# project_pcb.net
KiCad netlist of a schematic drawn in EAGLE
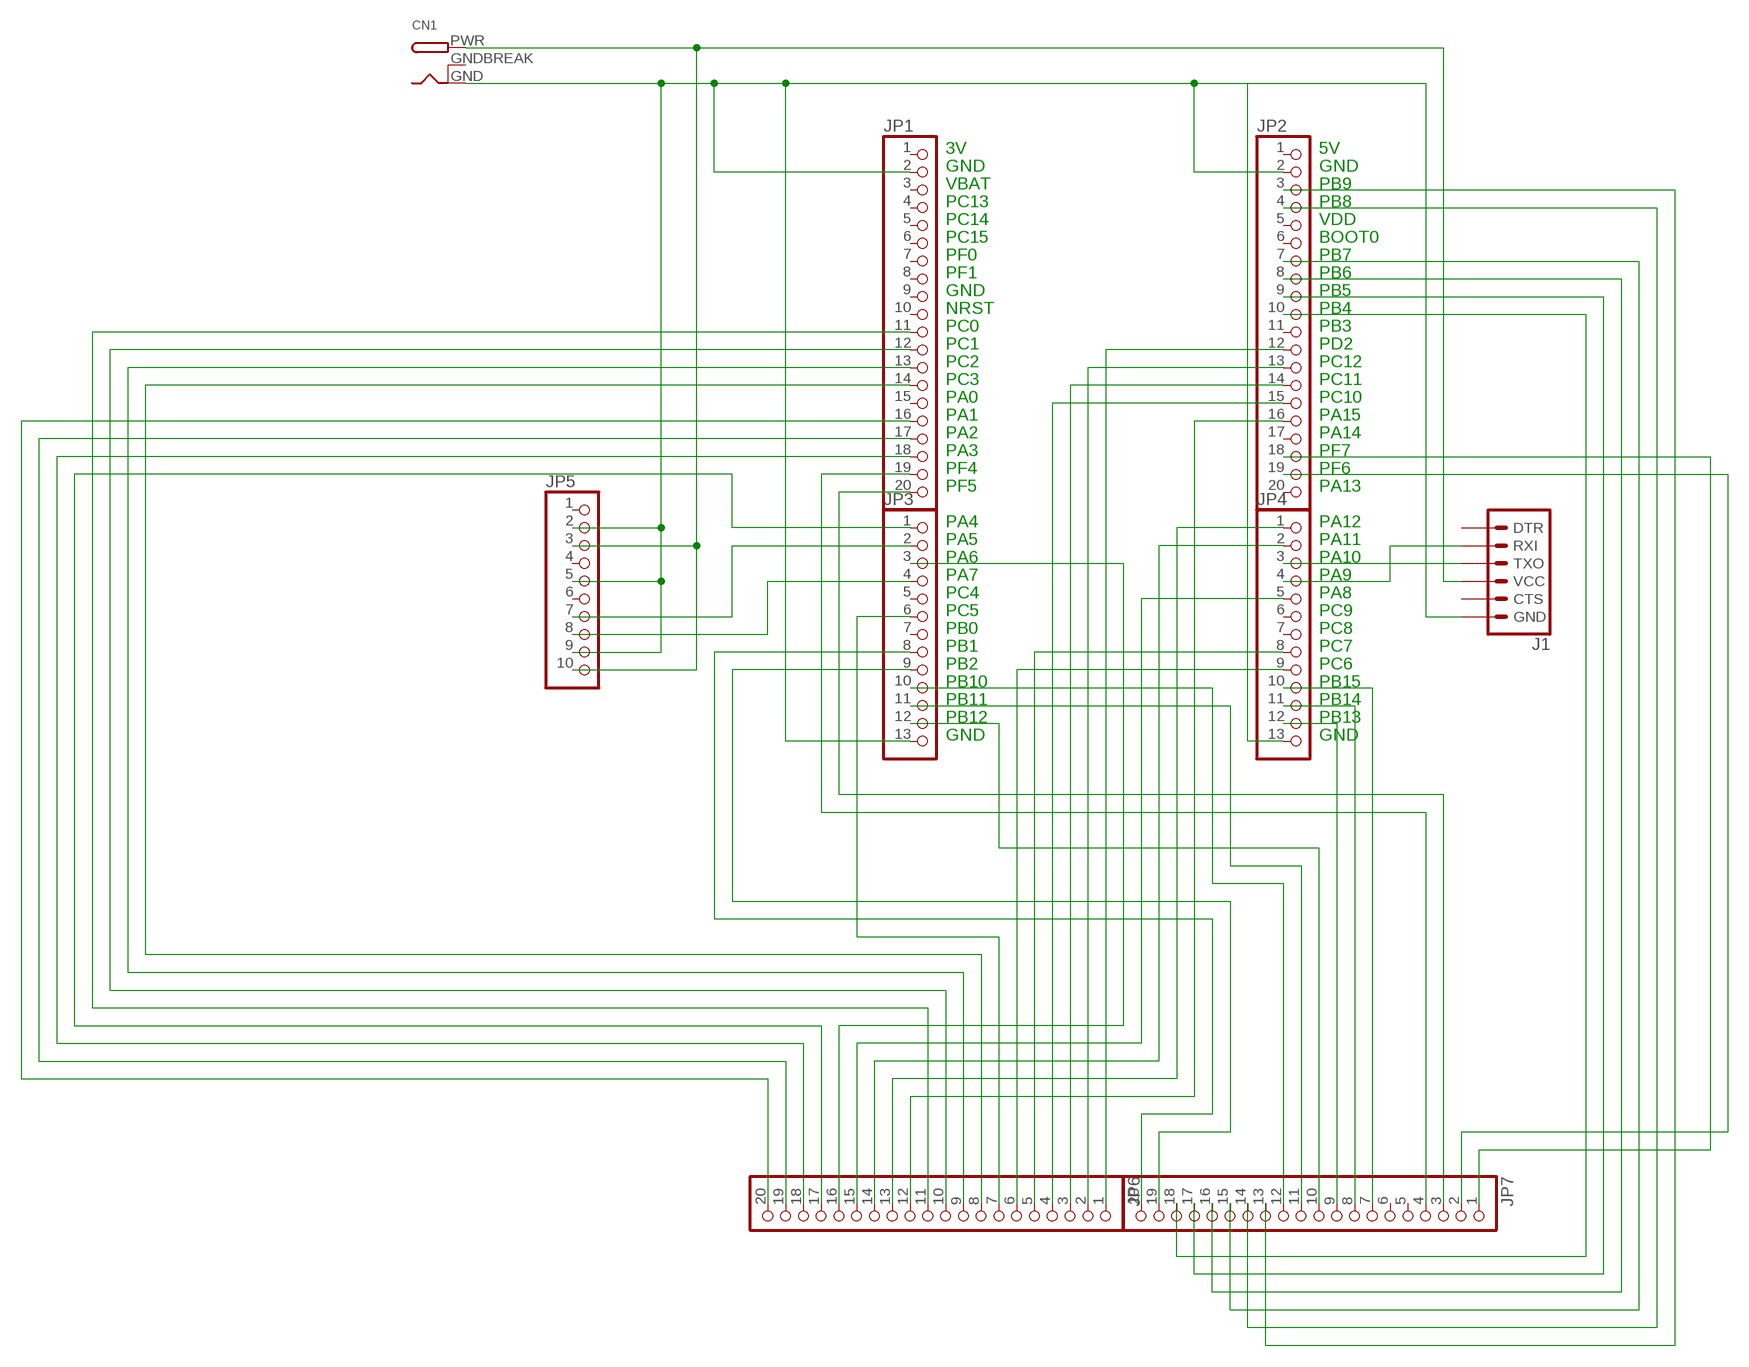
[diagram p0: schematic, sheet 1]

(export (version "E")
  (design (tool "Eeschema 10.0.6"))
  (components
    (comp (ref "CN1")
      (value "DCBARRELPTH")
      (footprint "eagle-import:DCJACK_2MM_PTH")
      (libsource (lib "eagle-import") (part "DCBARRELPTH"))
    )
    (comp (ref "J1")
      (value "6_PIN_SERIAL_TARGET")
      (footprint "eagle-import:1X06")
      (libsource (lib "eagle-import") (part "6_PIN_SERIAL_TARGET"))
    )
    (comp (ref "JP1")
      (value "PINHD-1X20")
      (footprint "eagle-import:1X20")
      (libsource (lib "eagle-import") (part "PINHD-1X20"))
    )
    (comp (ref "JP2")
      (value "PINHD-1X20")
      (footprint "eagle-import:1X20")
      (libsource (lib "eagle-import") (part "PINHD-1X20"))
    )
    (comp (ref "JP3")
      (value "PINHD-1X13")
      (footprint "eagle-import:1X13")
      (libsource (lib "eagle-import") (part "PINHD-1X13"))
    )
    (comp (ref "JP4")
      (value "PINHD-1X13")
      (footprint "eagle-import:1X13")
      (libsource (lib "eagle-import") (part "PINHD-1X13"))
    )
    (comp (ref "JP5")
      (value "PINHD-1X10")
      (footprint "eagle-import:1X10")
      (libsource (lib "eagle-import") (part "PINHD-1X10"))
    )
    (comp (ref "JP6")
      (value "PINHD-1X20")
      (footprint "eagle-import:1X20")
      (libsource (lib "eagle-import") (part "PINHD-1X20"))
    )
    (comp (ref "JP7")
      (value "PINHD-1X20")
      (footprint "eagle-import:1X20")
      (libsource (lib "eagle-import") (part "PINHD-1X20"))
    )
  )
  (nets
    (net (code "1") (name "/GNDBREAK") (class "Default")
      (node (ref "CN1") (pin "GNDBREAK") (pinfunction "GNDBREAK_GNDBREAK") (pintype "power_in"))
    )
    (net (code "2") (name "Net-(J1-GND)") (class "Default")
      (node (ref "CN1") (pin "GND") (pinfunction "GND_GND") (pintype "power_in"))
      (node (ref "J1") (pin "6") (pinfunction "GND_6") (pintype "passive"))
      (node (ref "JP1") (pin "2") (pinfunction "2_2") (pintype "passive"))
      (node (ref "JP2") (pin "2") (pinfunction "2_2") (pintype "passive"))
      (node (ref "JP3") (pin "13") (pinfunction "13_13") (pintype "passive"))
      (node (ref "JP4") (pin "13") (pinfunction "13_13") (pintype "passive"))
      (node (ref "JP5") (pin "2") (pinfunction "2_2") (pintype "passive"))
      (node (ref "JP5") (pin "5") (pinfunction "5_5") (pintype "passive"))
      (node (ref "JP5") (pin "9") (pinfunction "9_9") (pintype "passive"))
    )
    (net (code "3") (name "Net-(J1-RXI)") (class "Default")
      (node (ref "J1") (pin "2") (pinfunction "RXI_2") (pintype "passive"))
      (node (ref "JP4") (pin "4") (pinfunction "4_4") (pintype "passive"))
    )
    (net (code "4") (name "Net-(J1-TXO)") (class "Default")
      (node (ref "J1") (pin "3") (pinfunction "TXO_3") (pintype "passive"))
      (node (ref "JP4") (pin "3") (pinfunction "3_3") (pintype "passive"))
    )
    (net (code "5") (name "Net-(J1-VCC)") (class "Default")
      (node (ref "CN1") (pin "PWR") (pinfunction "PWR_PWR") (pintype "power_in"))
      (node (ref "J1") (pin "4") (pinfunction "VCC_4") (pintype "passive"))
      (node (ref "JP5") (pin "10") (pinfunction "10_10") (pintype "passive"))
      (node (ref "JP5") (pin "3") (pinfunction "3_3") (pintype "passive"))
    )
    (net (code "6") (name "Net-(JP1-Pad11)") (class "Default")
      (node (ref "JP1") (pin "11") (pinfunction "11_11") (pintype "passive"))
      (node (ref "JP6") (pin "11") (pinfunction "11_11") (pintype "passive"))
    )
    (net (code "7") (name "Net-(JP1-Pad12)") (class "Default")
      (node (ref "JP1") (pin "12") (pinfunction "12_12") (pintype "passive"))
      (node (ref "JP6") (pin "10") (pinfunction "10_10") (pintype "passive"))
    )
    (net (code "8") (name "Net-(JP1-Pad13)") (class "Default")
      (node (ref "JP1") (pin "13") (pinfunction "13_13") (pintype "passive"))
      (node (ref "JP6") (pin "9") (pinfunction "9_9") (pintype "passive"))
    )
    (net (code "9") (name "Net-(JP1-Pad14)") (class "Default")
      (node (ref "JP1") (pin "14") (pinfunction "14_14") (pintype "passive"))
      (node (ref "JP6") (pin "8") (pinfunction "8_8") (pintype "passive"))
    )
    (net (code "10") (name "Net-(JP1-Pad16)") (class "Default")
      (node (ref "JP1") (pin "16") (pinfunction "16_16") (pintype "passive"))
      (node (ref "JP6") (pin "20") (pinfunction "20_20") (pintype "passive"))
    )
    (net (code "11") (name "Net-(JP1-Pad17)") (class "Default")
      (node (ref "JP1") (pin "17") (pinfunction "17_17") (pintype "passive"))
      (node (ref "JP6") (pin "19") (pinfunction "19_19") (pintype "passive"))
    )
    (net (code "12") (name "Net-(JP1-Pad18)") (class "Default")
      (node (ref "JP1") (pin "18") (pinfunction "18_18") (pintype "passive"))
      (node (ref "JP6") (pin "18") (pinfunction "18_18") (pintype "passive"))
    )
    (net (code "13") (name "Net-(JP1-Pad19)") (class "Default")
      (node (ref "JP1") (pin "19") (pinfunction "19_19") (pintype "passive"))
      (node (ref "JP7") (pin "4") (pinfunction "4_4") (pintype "passive"))
    )
    (net (code "14") (name "Net-(JP1-Pad20)") (class "Default")
      (node (ref "JP1") (pin "20") (pinfunction "20_20") (pintype "passive"))
      (node (ref "JP7") (pin "3") (pinfunction "3_3") (pintype "passive"))
    )
    (net (code "15") (name "Net-(JP2-Pad3)") (class "Default")
      (node (ref "JP2") (pin "3") (pinfunction "3_3") (pintype "passive"))
      (node (ref "JP7") (pin "13") (pinfunction "13_13") (pintype "passive"))
    )
    (net (code "16") (name "Net-(JP2-Pad4)") (class "Default")
      (node (ref "JP2") (pin "4") (pinfunction "4_4") (pintype "passive"))
      (node (ref "JP7") (pin "14") (pinfunction "14_14") (pintype "passive"))
    )
    (net (code "17") (name "Net-(JP2-Pad7)") (class "Default")
      (node (ref "JP2") (pin "7") (pinfunction "7_7") (pintype "passive"))
      (node (ref "JP7") (pin "15") (pinfunction "15_15") (pintype "passive"))
    )
    (net (code "18") (name "Net-(JP2-Pad8)") (class "Default")
      (node (ref "JP2") (pin "8") (pinfunction "8_8") (pintype "passive"))
      (node (ref "JP7") (pin "16") (pinfunction "16_16") (pintype "passive"))
    )
    (net (code "19") (name "Net-(JP2-Pad9)") (class "Default")
      (node (ref "JP2") (pin "9") (pinfunction "9_9") (pintype "passive"))
      (node (ref "JP7") (pin "17") (pinfunction "17_17") (pintype "passive"))
    )
    (net (code "20") (name "Net-(JP2-Pad10)") (class "Default")
      (node (ref "JP2") (pin "10") (pinfunction "10_10") (pintype "passive"))
      (node (ref "JP7") (pin "18") (pinfunction "18_18") (pintype "passive"))
    )
    (net (code "21") (name "Net-(JP2-Pad12)") (class "Default")
      (node (ref "JP2") (pin "12") (pinfunction "12_12") (pintype "passive"))
      (node (ref "JP6") (pin "1") (pinfunction "1_1") (pintype "passive"))
    )
    (net (code "22") (name "Net-(JP2-Pad13)") (class "Default")
      (node (ref "JP2") (pin "13") (pinfunction "13_13") (pintype "passive"))
      (node (ref "JP6") (pin "2") (pinfunction "2_2") (pintype "passive"))
    )
    (net (code "23") (name "Net-(JP2-Pad14)") (class "Default")
      (node (ref "JP2") (pin "14") (pinfunction "14_14") (pintype "passive"))
      (node (ref "JP6") (pin "3") (pinfunction "3_3") (pintype "passive"))
    )
    (net (code "24") (name "Net-(JP2-Pad15)") (class "Default")
      (node (ref "JP2") (pin "15") (pinfunction "15_15") (pintype "passive"))
      (node (ref "JP6") (pin "4") (pinfunction "4_4") (pintype "passive"))
    )
    (net (code "25") (name "Net-(JP2-Pad16)") (class "Default")
      (node (ref "JP2") (pin "16") (pinfunction "16_16") (pintype "passive"))
      (node (ref "JP6") (pin "12") (pinfunction "12_12") (pintype "passive"))
    )
    (net (code "26") (name "Net-(JP2-Pad18)") (class "Default")
      (node (ref "JP2") (pin "18") (pinfunction "18_18") (pintype "passive"))
      (node (ref "JP7") (pin "1") (pinfunction "1_1") (pintype "passive"))
    )
    (net (code "27") (name "Net-(JP2-Pad19)") (class "Default")
      (node (ref "JP2") (pin "19") (pinfunction "19_19") (pintype "passive"))
      (node (ref "JP7") (pin "2") (pinfunction "2_2") (pintype "passive"))
    )
    (net (code "28") (name "Net-(JP3-Pad1)") (class "Default")
      (node (ref "JP3") (pin "1") (pinfunction "1_1") (pintype "passive"))
      (node (ref "JP6") (pin "17") (pinfunction "17_17") (pintype "passive"))
    )
    (net (code "29") (name "Net-(JP3-Pad2)") (class "Default")
      (node (ref "JP3") (pin "2") (pinfunction "2_2") (pintype "passive"))
      (node (ref "JP5") (pin "7") (pinfunction "7_7") (pintype "passive"))
    )
    (net (code "30") (name "Net-(JP3-Pad3)") (class "Default")
      (node (ref "JP3") (pin "3") (pinfunction "3_3") (pintype "passive"))
      (node (ref "JP6") (pin "16") (pinfunction "16_16") (pintype "passive"))
    )
    (net (code "31") (name "Net-(JP3-Pad4)") (class "Default")
      (node (ref "JP3") (pin "4") (pinfunction "4_4") (pintype "passive"))
      (node (ref "JP5") (pin "8") (pinfunction "8_8") (pintype "passive"))
    )
    (net (code "32") (name "Net-(JP3-Pad6)") (class "Default")
      (node (ref "JP3") (pin "6") (pinfunction "6_6") (pintype "passive"))
      (node (ref "JP6") (pin "7") (pinfunction "7_7") (pintype "passive"))
    )
    (net (code "33") (name "Net-(JP3-Pad8)") (class "Default")
      (node (ref "JP3") (pin "8") (pinfunction "8_8") (pintype "passive"))
      (node (ref "JP7") (pin "20") (pinfunction "20_20") (pintype "passive"))
    )
    (net (code "34") (name "Net-(JP3-Pad9)") (class "Default")
      (node (ref "JP3") (pin "9") (pinfunction "9_9") (pintype "passive"))
      (node (ref "JP7") (pin "19") (pinfunction "19_19") (pintype "passive"))
    )
    (net (code "35") (name "Net-(JP3-Pad10)") (class "Default")
      (node (ref "JP3") (pin "10") (pinfunction "10_10") (pintype "passive"))
      (node (ref "JP7") (pin "12") (pinfunction "12_12") (pintype "passive"))
    )
    (net (code "36") (name "Net-(JP3-Pad11)") (class "Default")
      (node (ref "JP3") (pin "11") (pinfunction "11_11") (pintype "passive"))
      (node (ref "JP7") (pin "11") (pinfunction "11_11") (pintype "passive"))
    )
    (net (code "37") (name "Net-(JP3-Pad12)") (class "Default")
      (node (ref "JP3") (pin "12") (pinfunction "12_12") (pintype "passive"))
      (node (ref "JP7") (pin "10") (pinfunction "10_10") (pintype "passive"))
    )
    (net (code "38") (name "Net-(JP4-Pad1)") (class "Default")
      (node (ref "JP4") (pin "1") (pinfunction "1_1") (pintype "passive"))
      (node (ref "JP6") (pin "13") (pinfunction "13_13") (pintype "passive"))
    )
    (net (code "39") (name "Net-(JP4-Pad2)") (class "Default")
      (node (ref "JP4") (pin "2") (pinfunction "2_2") (pintype "passive"))
      (node (ref "JP6") (pin "14") (pinfunction "14_14") (pintype "passive"))
    )
    (net (code "40") (name "Net-(JP4-Pad5)") (class "Default")
      (node (ref "JP4") (pin "5") (pinfunction "5_5") (pintype "passive"))
      (node (ref "JP6") (pin "15") (pinfunction "15_15") (pintype "passive"))
    )
    (net (code "41") (name "Net-(JP4-Pad8)") (class "Default")
      (node (ref "JP4") (pin "8") (pinfunction "8_8") (pintype "passive"))
      (node (ref "JP6") (pin "5") (pinfunction "5_5") (pintype "passive"))
    )
    (net (code "42") (name "Net-(JP4-Pad9)") (class "Default")
      (node (ref "JP4") (pin "9") (pinfunction "9_9") (pintype "passive"))
      (node (ref "JP6") (pin "6") (pinfunction "6_6") (pintype "passive"))
    )
    (net (code "43") (name "Net-(JP4-Pad10)") (class "Default")
      (node (ref "JP4") (pin "10") (pinfunction "10_10") (pintype "passive"))
      (node (ref "JP7") (pin "7") (pinfunction "7_7") (pintype "passive"))
    )
    (net (code "44") (name "Net-(JP4-Pad11)") (class "Default")
      (node (ref "JP4") (pin "11") (pinfunction "11_11") (pintype "passive"))
      (node (ref "JP7") (pin "8") (pinfunction "8_8") (pintype "passive"))
    )
    (net (code "45") (name "Net-(JP4-Pad12)") (class "Default")
      (node (ref "JP4") (pin "12") (pinfunction "12_12") (pintype "passive"))
      (node (ref "JP7") (pin "9") (pinfunction "9_9") (pintype "passive"))
    )
    (net (code "46") (name "unconnected-(J1-CTS-Pad5)") (class "Default")
      (node (ref "J1") (pin "5") (pinfunction "CTS_5") (pintype "passive"))
    )
    (net (code "47") (name "unconnected-(J1-DTR-Pad1)") (class "Default")
      (node (ref "J1") (pin "1") (pinfunction "DTR_1") (pintype "passive"))
    )
    (net (code "48") (name "unconnected-(JP1-Pad1)") (class "Default")
      (node (ref "JP1") (pin "1") (pinfunction "1_1") (pintype "passive"))
    )
    (net (code "49") (name "unconnected-(JP1-Pad3)") (class "Default")
      (node (ref "JP1") (pin "3") (pinfunction "3_3") (pintype "passive"))
    )
    (net (code "50") (name "unconnected-(JP1-Pad4)") (class "Default")
      (node (ref "JP1") (pin "4") (pinfunction "4_4") (pintype "passive"))
    )
    (net (code "51") (name "unconnected-(JP1-Pad5)") (class "Default")
      (node (ref "JP1") (pin "5") (pinfunction "5_5") (pintype "passive"))
    )
    (net (code "52") (name "unconnected-(JP1-Pad6)") (class "Default")
      (node (ref "JP1") (pin "6") (pinfunction "6_6") (pintype "passive"))
    )
    (net (code "53") (name "unconnected-(JP1-Pad7)") (class "Default")
      (node (ref "JP1") (pin "7") (pinfunction "7_7") (pintype "passive"))
    )
    (net (code "54") (name "unconnected-(JP1-Pad8)") (class "Default")
      (node (ref "JP1") (pin "8") (pinfunction "8_8") (pintype "passive"))
    )
    (net (code "55") (name "unconnected-(JP1-Pad9)") (class "Default")
      (node (ref "JP1") (pin "9") (pinfunction "9_9") (pintype "passive"))
    )
    (net (code "56") (name "unconnected-(JP1-Pad10)") (class "Default")
      (node (ref "JP1") (pin "10") (pinfunction "10_10") (pintype "passive"))
    )
    (net (code "57") (name "unconnected-(JP1-Pad15)") (class "Default")
      (node (ref "JP1") (pin "15") (pinfunction "15_15") (pintype "passive"))
    )
    (net (code "58") (name "unconnected-(JP2-Pad1)") (class "Default")
      (node (ref "JP2") (pin "1") (pinfunction "1_1") (pintype "passive"))
    )
    (net (code "59") (name "unconnected-(JP2-Pad5)") (class "Default")
      (node (ref "JP2") (pin "5") (pinfunction "5_5") (pintype "passive"))
    )
    (net (code "60") (name "unconnected-(JP2-Pad6)") (class "Default")
      (node (ref "JP2") (pin "6") (pinfunction "6_6") (pintype "passive"))
    )
    (net (code "61") (name "unconnected-(JP2-Pad11)") (class "Default")
      (node (ref "JP2") (pin "11") (pinfunction "11_11") (pintype "passive"))
    )
    (net (code "62") (name "unconnected-(JP2-Pad17)") (class "Default")
      (node (ref "JP2") (pin "17") (pinfunction "17_17") (pintype "passive"))
    )
    (net (code "63") (name "unconnected-(JP2-Pad20)") (class "Default")
      (node (ref "JP2") (pin "20") (pinfunction "20_20") (pintype "passive"))
    )
    (net (code "64") (name "unconnected-(JP3-Pad5)") (class "Default")
      (node (ref "JP3") (pin "5") (pinfunction "5_5") (pintype "passive"))
    )
    (net (code "65") (name "unconnected-(JP3-Pad7)") (class "Default")
      (node (ref "JP3") (pin "7") (pinfunction "7_7") (pintype "passive"))
    )
    (net (code "66") (name "unconnected-(JP4-Pad6)") (class "Default")
      (node (ref "JP4") (pin "6") (pinfunction "6_6") (pintype "passive"))
    )
    (net (code "67") (name "unconnected-(JP4-Pad7)") (class "Default")
      (node (ref "JP4") (pin "7") (pinfunction "7_7") (pintype "passive"))
    )
    (net (code "68") (name "unconnected-(JP5-Pad1)") (class "Default")
      (node (ref "JP5") (pin "1") (pinfunction "1_1") (pintype "passive"))
    )
    (net (code "69") (name "unconnected-(JP5-Pad4)") (class "Default")
      (node (ref "JP5") (pin "4") (pinfunction "4_4") (pintype "passive"))
    )
    (net (code "70") (name "unconnected-(JP5-Pad6)") (class "Default")
      (node (ref "JP5") (pin "6") (pinfunction "6_6") (pintype "passive"))
    )
    (net (code "71") (name "unconnected-(JP7-Pad5)") (class "Default")
      (node (ref "JP7") (pin "5") (pinfunction "5_5") (pintype "passive"))
    )
    (net (code "72") (name "unconnected-(JP7-Pad6)") (class "Default")
      (node (ref "JP7") (pin "6") (pinfunction "6_6") (pintype "passive"))
    )
  )
)
